# Servo.net
KiCad netlist of a schematic drawn in Altium Designer
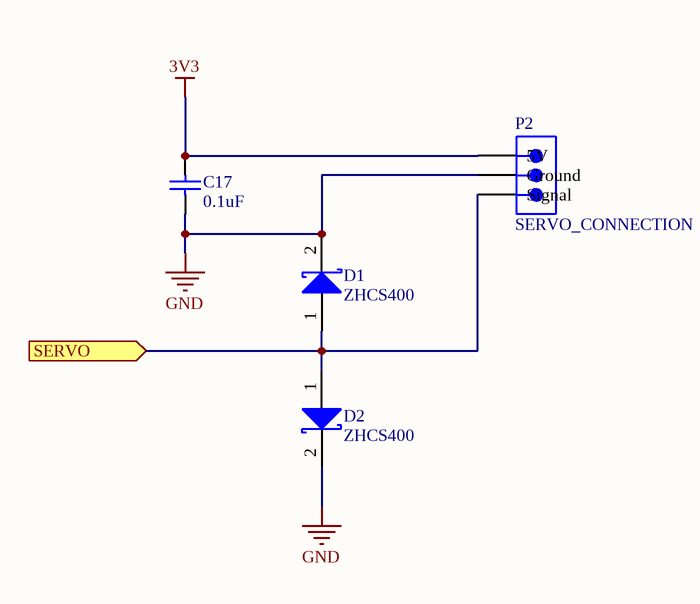
[diagram p0: Servo.SchDoc]

(export (version "E")
  (design (tool "Eeschema 10.0.6"))
  (components
    (comp (ref "C17")
      (value "0.1uF")
      (footprint "CAPC1608X90X35LL15T15")
      (description "Chip Capacitor, 100 nF, +/- 10%, 50 V, -55 to 125 degC, 0603 (1608 Metric), RoHS, Tape and Reel")
      (fields (field (name "TOLERANCE") "10%"))
      (libsource (lib "Altium Content Vault") (part "CAP-NP-2"))
    )
    (comp (ref "D1")
      (value "ZHCS400")
      (footprint "DIOD-SOD323-2_V")
      (description "Schottky Diode, 400mA")
      (fields (field (name "MANUFACTURER") "Diodes Inc"))
      (libsource (lib "Altium Content Vault") (part "DIOD-DSKY-A1K2-2"))
    )
    (comp (ref "D2")
      (value "ZHCS400")
      (footprint "DIOD-SOD323-2_V")
      (description "Schottky Diode, 400mA")
      (fields (field (name "MANUFACTURER") "Diodes Inc"))
      (libsource (lib "Altium Content Vault") (part "DIOD-DSKY-A1K2-2"))
    )
    (comp (ref "P2")
      (value "SERVO_CONNECTION")
      (footprint "SMTC-TSW-103-07-X-S")
      (description "0.025\" SQ Post Header, Through-hole, Vertical, -55 to 125 degC, 2.54 mm Pitch, 3-Pin, Male, RoHS")
      (fields (field (name "MANUFACTURER") "Samtec") (field (name "PARTNUMBER") "TSW-103-07-L-S"))
      (libsource (lib "Altium Content Vault") (part "SMTC-TSW-103-X-X-S-X"))
    )
  )
  (nets
    (net (code "1") (name "/SERVO") (class "Default")
      (node (ref "D1") (pin "1") (pinfunction "A_1") (pintype "passive"))
      (node (ref "D2") (pin "1") (pinfunction "A_1") (pintype "passive"))
      (node (ref "P2") (pin "3") (pinfunction "Signal_3") (pintype "passive"))
    )
    (net (code "2") (name "3V3") (class "Default")
      (node (ref "C17") (pin "2") (pinfunction "2_2") (pintype "passive"))
      (node (ref "P2") (pin "1") (pinfunction "5V_1") (pintype "passive"))
    )
    (net (code "3") (name "GND") (class "Default")
      (node (ref "C17") (pin "1") (pinfunction "1_1") (pintype "passive"))
      (node (ref "D1") (pin "2") (pinfunction "K_2") (pintype "passive"))
      (node (ref "D2") (pin "2") (pinfunction "K_2") (pintype "passive"))
      (node (ref "P2") (pin "2") (pinfunction "Ground_2") (pintype "passive"))
    )
  )
)
